# Programmer.net
KiCad netlist of a schematic drawn in EAGLE
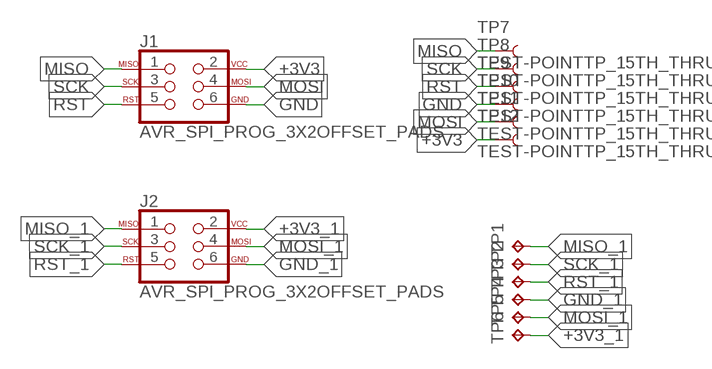
[diagram p0: schematic, sheet 1]

(export (version "E")
  (design (tool "Eeschema 10.0.6"))
  (components
    (comp (ref "J1")
      (value "AVR_SPI_PROG_3X2OFFSET_PADS")
      (footprint "eagle-import:2X3_OFFSET")
      (libsource (lib "eagle-import") (part "AVR_SPI_PROG_3X2OFFSET_PADS"))
    )
    (comp (ref "J2")
      (value "AVR_SPI_PROG_3X2OFFSET_PADS")
      (footprint "eagle-import:2X3_OFFSET")
      (libsource (lib "eagle-import") (part "AVR_SPI_PROG_3X2OFFSET_PADS"))
    )
    (comp (ref "TP1")
      (value "TPTP12SQ")
      (footprint "eagle-import:TP12SQ")
      (libsource (lib "eagle-import") (part "TPTP12SQ"))
    )
    (comp (ref "TP2")
      (value "TPTP12SQ")
      (footprint "eagle-import:TP12SQ")
      (libsource (lib "eagle-import") (part "TPTP12SQ"))
    )
    (comp (ref "TP3")
      (value "TPTP12SQ")
      (footprint "eagle-import:TP12SQ")
      (libsource (lib "eagle-import") (part "TPTP12SQ"))
    )
    (comp (ref "TP4")
      (value "TPTP12SQ")
      (footprint "eagle-import:TP12SQ")
      (libsource (lib "eagle-import") (part "TPTP12SQ"))
    )
    (comp (ref "TP5")
      (value "TPTP12SQ")
      (footprint "eagle-import:TP12SQ")
      (libsource (lib "eagle-import") (part "TPTP12SQ"))
    )
    (comp (ref "TP6")
      (value "TPTP12SQ")
      (footprint "eagle-import:TP12SQ")
      (libsource (lib "eagle-import") (part "TPTP12SQ"))
    )
    (comp (ref "TP7")
      (value "TEST-POINTTP_15TH_THRU")
      (footprint "eagle-import:TP_15TH")
      (libsource (lib "eagle-import") (part "TEST-POINTTP_15TH_THRU"))
    )
    (comp (ref "TP8")
      (value "TEST-POINTTP_15TH_THRU")
      (footprint "eagle-import:TP_15TH")
      (libsource (lib "eagle-import") (part "TEST-POINTTP_15TH_THRU"))
    )
    (comp (ref "TP9")
      (value "TEST-POINTTP_15TH_THRU")
      (footprint "eagle-import:TP_15TH")
      (libsource (lib "eagle-import") (part "TEST-POINTTP_15TH_THRU"))
    )
    (comp (ref "TP10")
      (value "TEST-POINTTP_15TH_THRU")
      (footprint "eagle-import:TP_15TH")
      (libsource (lib "eagle-import") (part "TEST-POINTTP_15TH_THRU"))
    )
    (comp (ref "TP11")
      (value "TEST-POINTTP_15TH_THRU")
      (footprint "eagle-import:TP_15TH")
      (libsource (lib "eagle-import") (part "TEST-POINTTP_15TH_THRU"))
    )
    (comp (ref "TP12")
      (value "TEST-POINTTP_15TH_THRU")
      (footprint "eagle-import:TP_15TH")
      (libsource (lib "eagle-import") (part "TEST-POINTTP_15TH_THRU"))
    )
  )
  (nets
    (net (code "1") (name "+3V3") (class "Default")
      (node (ref "J1") (pin "2") (pinfunction "2_2") (pintype "passive"))
      (node (ref "TP12") (pin "P$1") (pinfunction "1_P$1") (pintype "bidirectional"))
    )
    (net (code "2") (name "+3V3_1") (class "Default")
      (node (ref "J2") (pin "2") (pinfunction "2_2") (pintype "passive"))
      (node (ref "TP6") (pin "TP") (pinfunction "TP_TP") (pintype "input"))
    )
    (net (code "3") (name "GND") (class "Default")
      (node (ref "J1") (pin "6") (pinfunction "6_6") (pintype "passive"))
      (node (ref "TP10") (pin "P$1") (pinfunction "1_P$1") (pintype "bidirectional"))
    )
    (net (code "4") (name "GND_1") (class "Default")
      (node (ref "J2") (pin "6") (pinfunction "6_6") (pintype "passive"))
      (node (ref "TP4") (pin "TP") (pinfunction "TP_TP") (pintype "input"))
    )
    (net (code "5") (name "MISO") (class "Default")
      (node (ref "J1") (pin "1") (pinfunction "1_1") (pintype "passive"))
      (node (ref "TP7") (pin "P$1") (pinfunction "1_P$1") (pintype "bidirectional"))
    )
    (net (code "6") (name "MISO_1") (class "Default")
      (node (ref "J2") (pin "1") (pinfunction "1_1") (pintype "passive"))
      (node (ref "TP1") (pin "TP") (pinfunction "TP_TP") (pintype "input"))
    )
    (net (code "7") (name "MOSI") (class "Default")
      (node (ref "J1") (pin "4") (pinfunction "4_4") (pintype "passive"))
      (node (ref "TP11") (pin "P$1") (pinfunction "1_P$1") (pintype "bidirectional"))
    )
    (net (code "8") (name "MOSI_1") (class "Default")
      (node (ref "J2") (pin "4") (pinfunction "4_4") (pintype "passive"))
      (node (ref "TP5") (pin "TP") (pinfunction "TP_TP") (pintype "input"))
    )
    (net (code "9") (name "RST") (class "Default")
      (node (ref "J1") (pin "5") (pinfunction "5_5") (pintype "passive"))
      (node (ref "TP9") (pin "P$1") (pinfunction "1_P$1") (pintype "bidirectional"))
    )
    (net (code "10") (name "RST_1") (class "Default")
      (node (ref "J2") (pin "5") (pinfunction "5_5") (pintype "passive"))
      (node (ref "TP3") (pin "TP") (pinfunction "TP_TP") (pintype "input"))
    )
    (net (code "11") (name "SCK") (class "Default")
      (node (ref "J1") (pin "3") (pinfunction "3_3") (pintype "passive"))
      (node (ref "TP8") (pin "P$1") (pinfunction "1_P$1") (pintype "bidirectional"))
    )
    (net (code "12") (name "SCK_1") (class "Default")
      (node (ref "J2") (pin "3") (pinfunction "3_3") (pintype "passive"))
      (node (ref "TP2") (pin "TP") (pinfunction "TP_TP") (pintype "input"))
    )
  )
)
